# Sheet1.net
KiCad netlist of a schematic drawn in Altium Designer
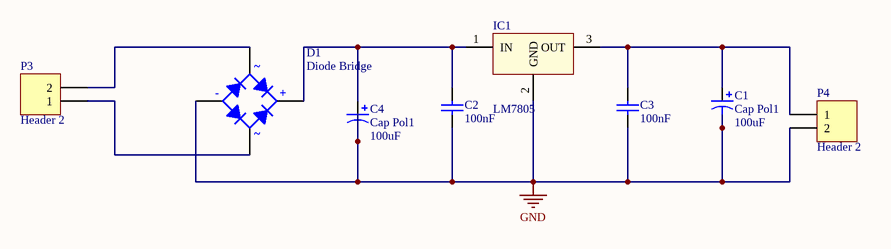
[diagram p0: Sheet1.SchDoc]

(export (version "E")
  (design (tool "Eeschema 10.0.6"))
  (components
    (comp (ref "C1")
      (value "Cap Pol1")
      (footprint "CAP_POL_3MM")
      (description "Polarized Capacitor (Radial)")
      (fields (field (name "ALTIUM_VALUE") "100uF") (field (name "PUBLISHER") "Altium Limited"))
      (libsource (lib "Miscellaneous Devices") (part "Cap Pol1"))
    )
    (comp (ref "C2")
      (value "100nF")
      (footprint "Cap Non Pol 3mm")
      (description "Cap Nol Pol")
      (libsource (lib "sch") (part "Cap Non Pol"))
    )
    (comp (ref "C3")
      (value "100nF")
      (footprint "Cap Non Pol 3mm")
      (description "Cap Nol Pol")
      (libsource (lib "sch") (part "Cap Non Pol"))
    )
    (comp (ref "C4")
      (value "Cap Pol1")
      (footprint "CAP_POL_3MM")
      (description "Polarized Capacitor (Radial)")
      (fields (field (name "ALTIUM_VALUE") "100uF") (field (name "PUBLISHER") "Altium Limited"))
      (libsource (lib "Miscellaneous Devices") (part "Cap Pol1"))
    )
    (comp (ref "D1")
      (value "Diode Bridge")
      (footprint "DIODE BRIDGE (1A)")
      (description "Full Wave Diode Bridge")
      (fields (field (name "PUBLISHER") "Altium Limited"))
      (libsource (lib "hphonglib") (part "Diode Bridge"))
    )
    (comp (ref "IC1")
      (value "LM7805")
      (footprint "QTO-220")
      (description "On ap +, from + 5 to + 24VDC")
      (libsource (lib "My Library") (part "LM78xx"))
    )
    (comp (ref "P3")
      (value "Header 2")
      (footprint "Header 2")
      (description "Header, 2-Pin")
      (fields (field (name "PUBLISHER") "Altium Limited"))
      (libsource (lib "") (part "Header 2_1"))
    )
    (comp (ref "P4")
      (value "Header 2")
      (footprint "Header 2")
      (description "Header, 2-Pin")
      (fields (field (name "PUBLISHER") "Altium Limited"))
      (libsource (lib "hphonglib") (part "Header 2"))
    )
  )
  (nets
    (net (code "1") (name "GND") (class "Default")
      (node (ref "C1") (pin "2") (pinfunction "2_2") (pintype "passive"))
      (node (ref "C2") (pin "1") (pinfunction "1_1") (pintype "passive"))
      (node (ref "C3") (pin "1") (pinfunction "1_1") (pintype "passive"))
      (node (ref "C4") (pin "2") (pinfunction "2_2") (pintype "passive"))
      (node (ref "D1") (pin "4") (pinfunction "A_4") (pintype "passive"))
      (node (ref "IC1") (pin "2") (pinfunction "GND_2") (pintype "passive"))
      (node (ref "P4") (pin "2") (pinfunction "2_2") (pintype "passive"))
    )
    (net (code "2") (name "Net-(D1-C-Pad2)") (class "Default")
      (node (ref "D1") (pin "2") (pinfunction "C_2") (pintype "passive"))
      (node (ref "P3") (pin "2") (pinfunction "2_2") (pintype "passive"))
    )
    (net (code "3") (name "Net-(D1-C-Pad3)") (class "Default")
      (node (ref "D1") (pin "3") (pinfunction "C_3") (pintype "passive"))
      (node (ref "P3") (pin "1") (pinfunction "1_1") (pintype "passive"))
    )
    (net (code "4") (name "Net-(D1-K)") (class "Default")
      (node (ref "C2") (pin "2") (pinfunction "2_2") (pintype "passive"))
      (node (ref "C4") (pin "1") (pinfunction "1_1") (pintype "passive"))
      (node (ref "D1") (pin "1") (pinfunction "K_1") (pintype "passive"))
      (node (ref "IC1") (pin "1") (pinfunction "IN_1") (pintype "passive"))
    )
    (net (code "5") (name "Net-(IC1-OUT)") (class "Default")
      (node (ref "C1") (pin "1") (pinfunction "1_1") (pintype "passive"))
      (node (ref "C3") (pin "2") (pinfunction "2_2") (pintype "passive"))
      (node (ref "IC1") (pin "3") (pinfunction "OUT_3") (pintype "passive"))
      (node (ref "P4") (pin "1") (pinfunction "1_1") (pintype "passive"))
    )
  )
)
